# SCBD-10-63HP.net
KiCad netlist of a schematic drawn in Altium Designer
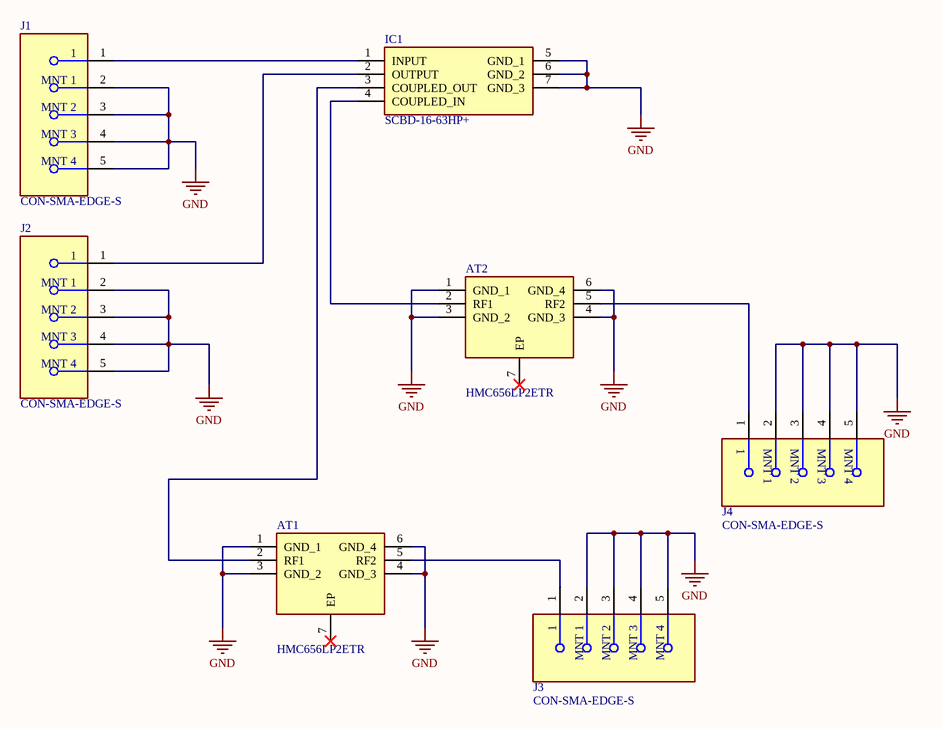
[diagram p0: SCBD-10-63HP.SchDoc]

(export (version "E")
  (design (tool "Eeschema 10.0.6"))
  (components
    (comp (ref "AT1")
      (value "HMC656LP2ETR")
      (footprint "SamacSys:SON65P200X200X100-7N")
      (description "Attenuator or Isolator")
      (fields (field (name "MOUSER PART NUMBER") "584-HMC656LP2ETR"))
      (libsource (lib "*") (part "HMC656LP2ETR"))
    )
    (comp (ref "AT2")
      (value "HMC656LP2ETR")
      (footprint "SamacSys:SON65P200X200X100-7N")
      (description "Attenuator or Isolator")
      (fields (field (name "MOUSER PART NUMBER") "584-HMC656LP2ETR"))
      (libsource (lib "*") (part "HMC656LP2ETR"))
    )
    (comp (ref "IC1")
      (value "SCBD-16-63HP+")
      (footprint "SamacSys:SCBD1663HP")
      (description "Integrated Circuit")
      (fields (field (name "MOUSER PART NUMBER") "139-SCBD-16-63HP"))
      (libsource (lib "*") (part "SCBD-16-63HP+"))
    )
    (comp (ref "J1")
      (value "CON-SMA-EDGE-S")
      (footprint "FP-CON-SMA-EDGE-S-MFG")
      (description "CONN SMA JACK STR EDGE MNT")
      (fields
        (field (name "OCTOPART") "https://octopart.com/con-sma-edge-s-rf+solutions-70967450")
        (field (name "MANUFACTURER") "RF Solutions Ltd.")
      )
      (libsource (lib "Altium Content Vault") (part "a163d97a771fcdd2fd1f1a9264c171f"))
    )
    (comp (ref "J2")
      (value "CON-SMA-EDGE-S")
      (footprint "FP-CON-SMA-EDGE-S-MFG")
      (description "CONN SMA JACK STR EDGE MNT")
      (fields
        (field (name "OCTOPART") "https://octopart.com/con-sma-edge-s-rf+solutions-70967450")
        (field (name "MANUFACTURER") "RF Solutions Ltd.")
      )
      (libsource (lib "Altium Content Vault") (part "a163d97a771fcdd2fd1f1a9264c171f"))
    )
    (comp (ref "J3")
      (value "CON-SMA-EDGE-S")
      (footprint "FP-CON-SMA-EDGE-S-MFG")
      (description "CONN SMA JACK STR EDGE MNT")
      (fields
        (field (name "OCTOPART") "https://octopart.com/con-sma-edge-s-rf+solutions-70967450")
        (field (name "MANUFACTURER") "RF Solutions Ltd.")
      )
      (libsource (lib "") (part "a163d97a771fcdd2fd1f1a9264c171f_1"))
    )
    (comp (ref "J4")
      (value "CON-SMA-EDGE-S")
      (footprint "FP-CON-SMA-EDGE-S-MFG")
      (description "CONN SMA JACK STR EDGE MNT")
      (fields
        (field (name "OCTOPART") "https://octopart.com/con-sma-edge-s-rf+solutions-70967450")
        (field (name "MANUFACTURER") "RF Solutions Ltd.")
      )
      (libsource (lib "") (part "a163d97a771fcdd2fd1f1a9264c171f_1"))
    )
  )
  (nets
    (net (code "1") (name "GND") (class "Default")
      (node (ref "AT1") (pin "1") (pinfunction "GND_1_1") (pintype "passive"))
      (node (ref "AT1") (pin "3") (pinfunction "GND_2_3") (pintype "passive"))
      (node (ref "AT1") (pin "4") (pinfunction "GND_3_4") (pintype "passive"))
      (node (ref "AT1") (pin "6") (pinfunction "GND_4_6") (pintype "passive"))
      (node (ref "AT2") (pin "1") (pinfunction "GND_1_1") (pintype "passive"))
      (node (ref "AT2") (pin "3") (pinfunction "GND_2_3") (pintype "passive"))
      (node (ref "AT2") (pin "4") (pinfunction "GND_3_4") (pintype "passive"))
      (node (ref "AT2") (pin "6") (pinfunction "GND_4_6") (pintype "passive"))
      (node (ref "IC1") (pin "5") (pinfunction "GND_1_5") (pintype "passive"))
      (node (ref "IC1") (pin "6") (pinfunction "GND_2_6") (pintype "passive"))
      (node (ref "IC1") (pin "7") (pinfunction "GND_3_7") (pintype "passive"))
      (node (ref "J1") (pin "2") (pinfunction "MNT_1_2") (pintype "passive"))
      (node (ref "J1") (pin "3") (pinfunction "MNT_2_3") (pintype "passive"))
      (node (ref "J1") (pin "4") (pinfunction "MNT_3_4") (pintype "passive"))
      (node (ref "J1") (pin "5") (pinfunction "MNT_4_5") (pintype "passive"))
      (node (ref "J2") (pin "2") (pinfunction "MNT_1_2") (pintype "passive"))
      (node (ref "J2") (pin "3") (pinfunction "MNT_2_3") (pintype "passive"))
      (node (ref "J2") (pin "4") (pinfunction "MNT_3_4") (pintype "passive"))
      (node (ref "J2") (pin "5") (pinfunction "MNT_4_5") (pintype "passive"))
      (node (ref "J3") (pin "2") (pinfunction "MNT_1_2") (pintype "passive"))
      (node (ref "J3") (pin "3") (pinfunction "MNT_2_3") (pintype "passive"))
      (node (ref "J3") (pin "4") (pinfunction "MNT_3_4") (pintype "passive"))
      (node (ref "J3") (pin "5") (pinfunction "MNT_4_5") (pintype "passive"))
      (node (ref "J4") (pin "2") (pinfunction "MNT_1_2") (pintype "passive"))
      (node (ref "J4") (pin "3") (pinfunction "MNT_2_3") (pintype "passive"))
      (node (ref "J4") (pin "4") (pinfunction "MNT_3_4") (pintype "passive"))
      (node (ref "J4") (pin "5") (pinfunction "MNT_4_5") (pintype "passive"))
    )
    (net (code "2") (name "Net-(AT1-RF1)") (class "Default")
      (node (ref "AT1") (pin "2") (pinfunction "RF1_2") (pintype "passive"))
      (node (ref "IC1") (pin "3") (pinfunction "COUPLED_OUT_3") (pintype "passive"))
    )
    (net (code "3") (name "Net-(AT1-RF2)") (class "Default")
      (node (ref "AT1") (pin "5") (pinfunction "RF2_5") (pintype "passive"))
      (node (ref "J3") (pin "1") (pinfunction "1_1") (pintype "passive"))
    )
    (net (code "4") (name "Net-(AT2-RF1)") (class "Default")
      (node (ref "AT2") (pin "2") (pinfunction "RF1_2") (pintype "passive"))
      (node (ref "IC1") (pin "4") (pinfunction "COUPLED_IN_4") (pintype "passive"))
    )
    (net (code "5") (name "Net-(AT2-RF2)") (class "Default")
      (node (ref "AT2") (pin "5") (pinfunction "RF2_5") (pintype "passive"))
      (node (ref "J4") (pin "1") (pinfunction "1_1") (pintype "passive"))
    )
    (net (code "6") (name "Net-(IC1-INPUT)") (class "Default")
      (node (ref "IC1") (pin "1") (pinfunction "INPUT_1") (pintype "passive"))
      (node (ref "J1") (pin "1") (pinfunction "1_1") (pintype "passive"))
    )
    (net (code "7") (name "Net-(IC1-OUTPUT)") (class "Default")
      (node (ref "IC1") (pin "2") (pinfunction "OUTPUT_2") (pintype "passive"))
      (node (ref "J2") (pin "1") (pinfunction "1_1") (pintype "passive"))
    )
    (net (code "8") (name "unconnected-(AT1-EP-Pad7)") (class "Default")
      (node (ref "AT1") (pin "7") (pinfunction "EP_7") (pintype "passive+no_connect"))
    )
    (net (code "9") (name "unconnected-(AT2-EP-Pad7)") (class "Default")
      (node (ref "AT2") (pin "7") (pinfunction "EP_7") (pintype "passive+no_connect"))
    )
  )
)
